# i2c-logic-level-converter.net
KiCad netlist of a schematic drawn in EAGLE
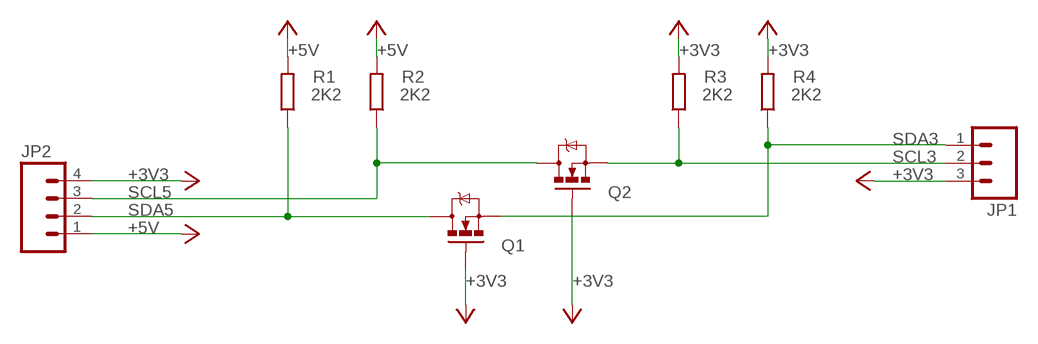
[diagram p0: schematic, sheet 1]

(export (version "E")
  (design (tool "Eeschema 10.0.6"))
  (components
    (comp (ref "JP1")
      (value "M03PTH")
      (footprint "eagle-import:1X03")
      (libsource (lib "eagle-import") (part "M03PTH"))
    )
    (comp (ref "JP2")
      (value "M04PTH")
      (footprint "eagle-import:1X04")
      (libsource (lib "eagle-import") (part "M04PTH"))
    )
    (comp (ref "Q1")
      (value "MOSFET-NCHANNELPTH")
      (footprint "eagle-import:TO-92")
      (libsource (lib "eagle-import") (part "MOSFET-NCHANNELPTH"))
    )
    (comp (ref "Q2")
      (value "MOSFET-NCHANNELPTH")
      (footprint "eagle-import:TO-92")
      (libsource (lib "eagle-import") (part "MOSFET-NCHANNELPTH"))
    )
    (comp (ref "R1")
      (value "2K2")
      (footprint "eagle-import:0204_5")
      (libsource (lib "eagle-import") (part "R-EU_0204/5"))
    )
    (comp (ref "R2")
      (value "2K2")
      (footprint "eagle-import:0204_5")
      (libsource (lib "eagle-import") (part "R-EU_0204/5"))
    )
    (comp (ref "R3")
      (value "2K2")
      (footprint "eagle-import:0204_5")
      (libsource (lib "eagle-import") (part "R-EU_0204/5"))
    )
    (comp (ref "R4")
      (value "2K2")
      (footprint "eagle-import:0204_5")
      (libsource (lib "eagle-import") (part "R-EU_0204/5"))
    )
  )
  (nets
    (net (code "1") (name "+3V3") (class "Default")
      (node (ref "JP1") (pin "3") (pinfunction "3_3") (pintype "passive"))
      (node (ref "JP2") (pin "4") (pinfunction "4_4") (pintype "passive"))
      (node (ref "Q1") (pin "3") (pinfunction "G_3") (pintype "passive"))
      (node (ref "Q2") (pin "3") (pinfunction "G_3") (pintype "passive"))
      (node (ref "R3") (pin "2") (pinfunction "2_2") (pintype "passive"))
      (node (ref "R4") (pin "2") (pinfunction "2_2") (pintype "passive"))
    )
    (net (code "2") (name "+5V") (class "Default")
      (node (ref "JP2") (pin "1") (pinfunction "1_1") (pintype "passive"))
      (node (ref "R1") (pin "2") (pinfunction "2_2") (pintype "passive"))
      (node (ref "R2") (pin "2") (pinfunction "2_2") (pintype "passive"))
    )
    (net (code "3") (name "/SCL3") (class "Default")
      (node (ref "JP1") (pin "2") (pinfunction "2_2") (pintype "passive"))
      (node (ref "Q2") (pin "2") (pinfunction "S_2") (pintype "passive"))
      (node (ref "R3") (pin "1") (pinfunction "1_1") (pintype "passive"))
    )
    (net (code "4") (name "/SCL5") (class "Default")
      (node (ref "JP2") (pin "3") (pinfunction "3_3") (pintype "passive"))
      (node (ref "Q2") (pin "1") (pinfunction "D_1") (pintype "passive"))
      (node (ref "R2") (pin "1") (pinfunction "1_1") (pintype "passive"))
    )
    (net (code "5") (name "/SDA3") (class "Default")
      (node (ref "JP1") (pin "1") (pinfunction "1_1") (pintype "passive"))
      (node (ref "Q1") (pin "2") (pinfunction "S_2") (pintype "passive"))
      (node (ref "R4") (pin "1") (pinfunction "1_1") (pintype "passive"))
    )
    (net (code "6") (name "/SDA5") (class "Default")
      (node (ref "JP2") (pin "2") (pinfunction "2_2") (pintype "passive"))
      (node (ref "Q1") (pin "1") (pinfunction "D_1") (pintype "passive"))
      (node (ref "R1") (pin "1") (pinfunction "1_1") (pintype "passive"))
    )
  )
)
